# clipper.net
KiCad netlist of a schematic drawn in EAGLE
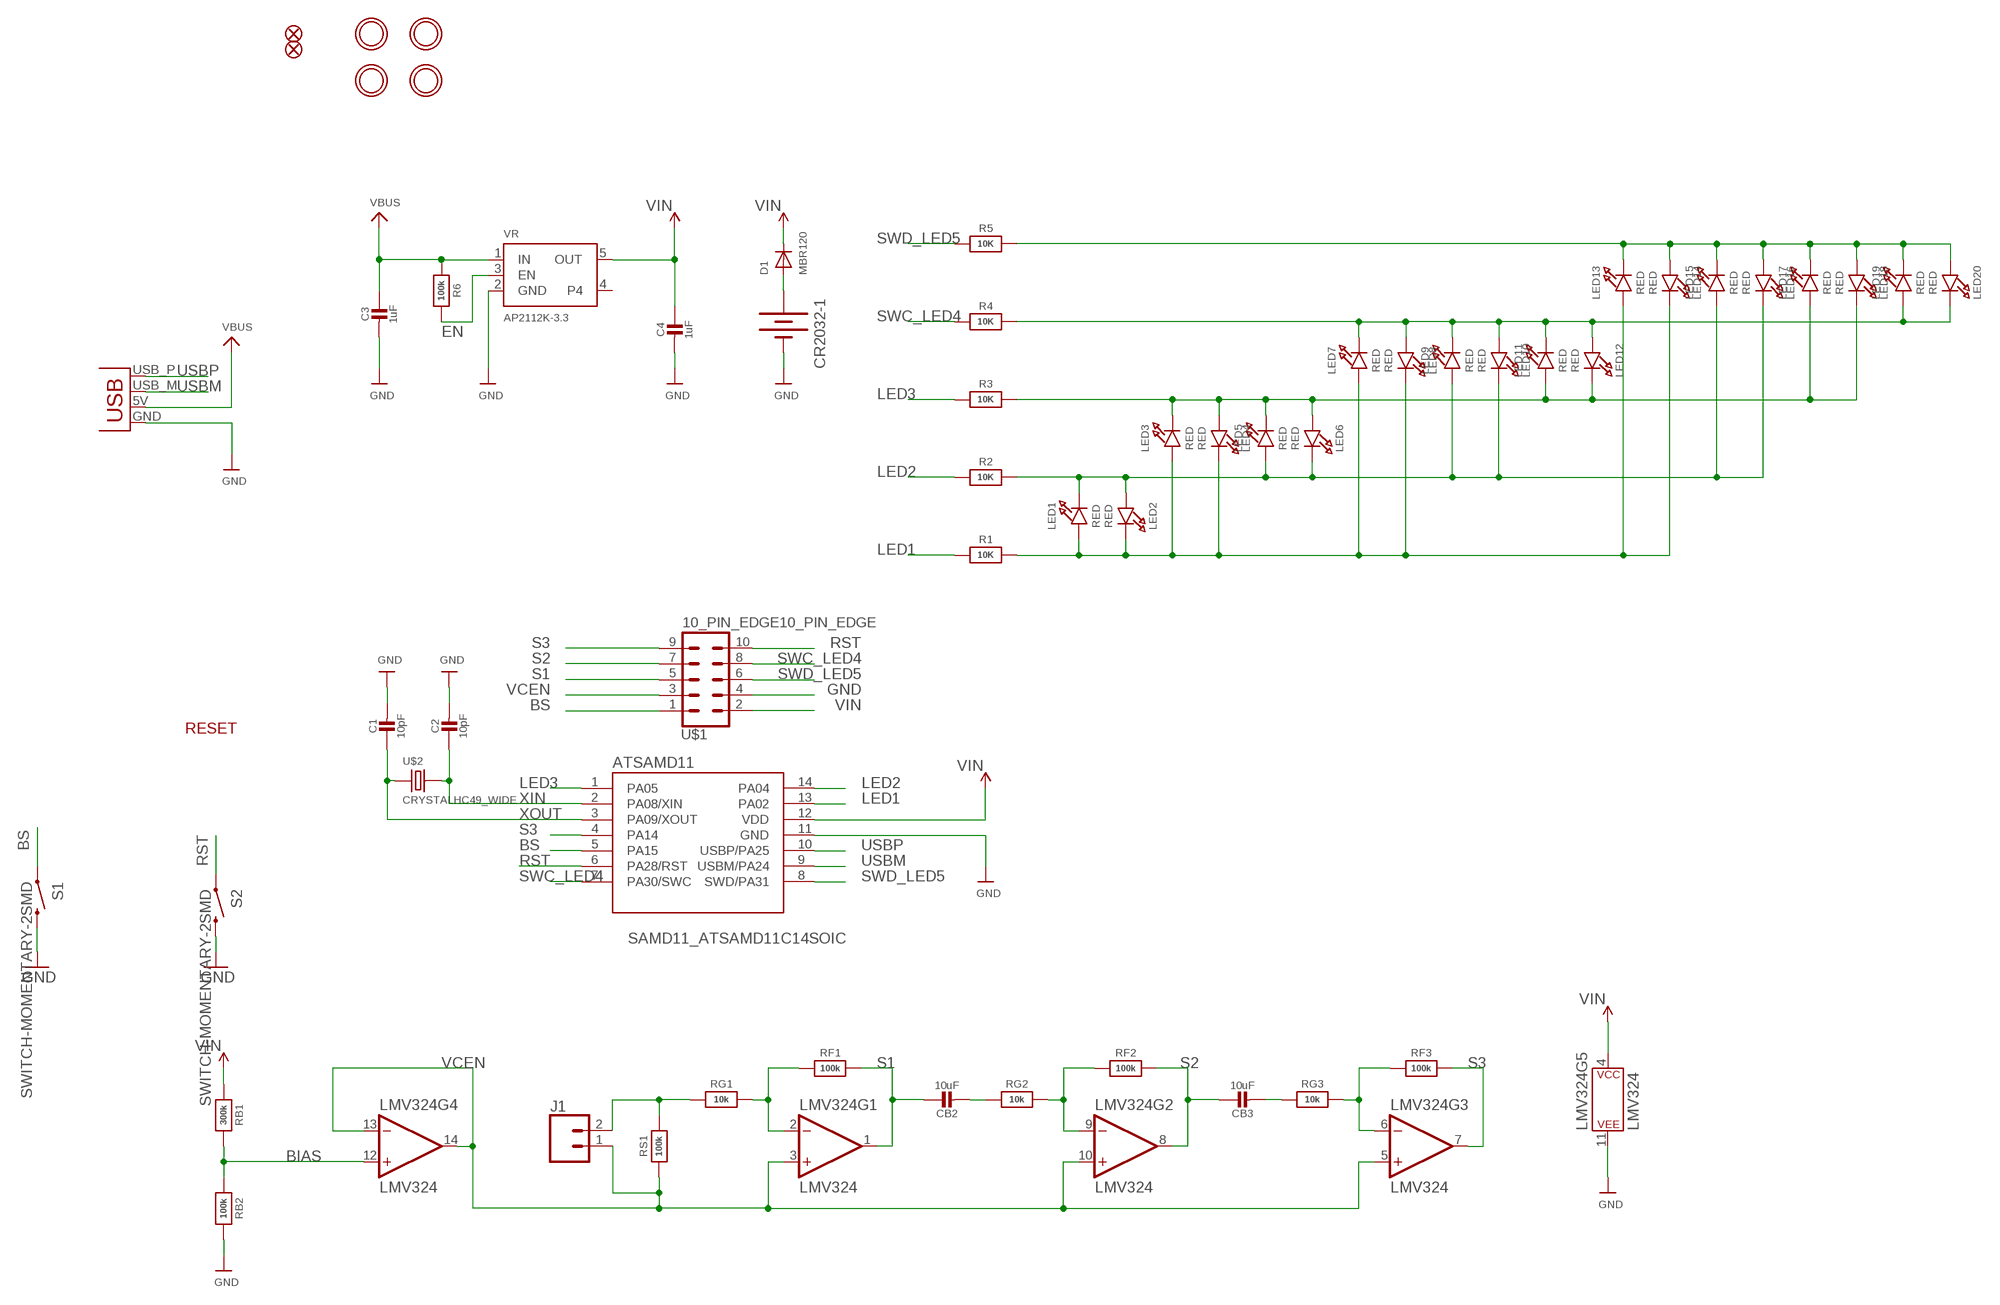
[diagram p0: schematic, sheet 1]

(export (version "E")
  (design (tool "Eeschema 10.0.6"))
  (components
    (comp (ref "ATSAMD11")
      (value "SAMD11_ATSAMD11C14SOIC")
      (footprint "eagle-import:RRACE001_SO14")
      (libsource (lib "eagle-import") (part "SAMD11_ATSAMD11C14SOIC"))
    )
    (comp (ref "C1")
      (value "10pF")
      (footprint "eagle-import:0603-NO")
      (libsource (lib "eagle-import") (part "CAP_CERAMIC0603_NO"))
    )
    (comp (ref "C2")
      (value "10pF")
      (footprint "eagle-import:0603-NO")
      (libsource (lib "eagle-import") (part "CAP_CERAMIC0603_NO"))
    )
    (comp (ref "C3")
      (value "1uF")
      (footprint "eagle-import:0603-NO")
      (libsource (lib "eagle-import") (part "CAP_CERAMIC0603_NO"))
    )
    (comp (ref "C4")
      (value "1uF")
      (footprint "eagle-import:0603-NO")
      (libsource (lib "eagle-import") (part "CAP_CERAMIC0603_NO"))
    )
    (comp (ref "CB2")
      (value "10uF")
      (footprint "eagle-import:0603-NO")
      (libsource (lib "eagle-import") (part "CAP_CERAMIC0603_NO"))
    )
    (comp (ref "CB3")
      (value "10uF")
      (footprint "eagle-import:0603-NO")
      (libsource (lib "eagle-import") (part "CAP_CERAMIC0603_NO"))
    )
    (comp (ref "CR2032-1")
      (value "BATTERY_20MM_PTH")
      (footprint "eagle-import:BATTCOM_20MM_PTH")
      (libsource (lib "eagle-import") (part "BATTERY_20MM_PTH"))
    )
    (comp (ref "D1")
      (value "MBR120")
      (footprint "eagle-import:SOD-123FL")
      (libsource (lib "eagle-import") (part "DIODE_SOD-123FL"))
    )
    (comp (ref "J1")
      (value "CONN_02")
      (footprint "eagle-import:1X02")
      (libsource (lib "eagle-import") (part "CONN_02"))
    )
    (comp (ref "LED1")
      (value "RED")
      (footprint "eagle-import:CHIPLED_0603_NOOUTLINE")
      (libsource (lib "eagle-import") (part "LED0603_NOOUTLINE"))
    )
    (comp (ref "LED2")
      (value "RED")
      (footprint "eagle-import:CHIPLED_0603_NOOUTLINE")
      (libsource (lib "eagle-import") (part "LED0603_NOOUTLINE"))
    )
    (comp (ref "LED3")
      (value "RED")
      (footprint "eagle-import:CHIPLED_0603_NOOUTLINE")
      (libsource (lib "eagle-import") (part "LED0603_NOOUTLINE"))
    )
    (comp (ref "LED4")
      (value "RED")
      (footprint "eagle-import:CHIPLED_0603_NOOUTLINE")
      (libsource (lib "eagle-import") (part "LED0603_NOOUTLINE"))
    )
    (comp (ref "LED5")
      (value "RED")
      (footprint "eagle-import:CHIPLED_0603_NOOUTLINE")
      (libsource (lib "eagle-import") (part "LED0603_NOOUTLINE"))
    )
    (comp (ref "LED6")
      (value "RED")
      (footprint "eagle-import:CHIPLED_0603_NOOUTLINE")
      (libsource (lib "eagle-import") (part "LED0603_NOOUTLINE"))
    )
    (comp (ref "LED7")
      (value "RED")
      (footprint "eagle-import:CHIPLED_0603_NOOUTLINE")
      (libsource (lib "eagle-import") (part "LED0603_NOOUTLINE"))
    )
    (comp (ref "LED8")
      (value "RED")
      (footprint "eagle-import:CHIPLED_0603_NOOUTLINE")
      (libsource (lib "eagle-import") (part "LED0603_NOOUTLINE"))
    )
    (comp (ref "LED9")
      (value "RED")
      (footprint "eagle-import:CHIPLED_0603_NOOUTLINE")
      (libsource (lib "eagle-import") (part "LED0603_NOOUTLINE"))
    )
    (comp (ref "LED10")
      (value "RED")
      (footprint "eagle-import:CHIPLED_0603_NOOUTLINE")
      (libsource (lib "eagle-import") (part "LED0603_NOOUTLINE"))
    )
    (comp (ref "LED11")
      (value "RED")
      (footprint "eagle-import:CHIPLED_0603_NOOUTLINE")
      (libsource (lib "eagle-import") (part "LED0603_NOOUTLINE"))
    )
    (comp (ref "LED12")
      (value "RED")
      (footprint "eagle-import:CHIPLED_0603_NOOUTLINE")
      (libsource (lib "eagle-import") (part "LED0603_NOOUTLINE"))
    )
    (comp (ref "LED13")
      (value "RED")
      (footprint "eagle-import:CHIPLED_0603_NOOUTLINE")
      (libsource (lib "eagle-import") (part "LED0603_NOOUTLINE"))
    )
    (comp (ref "LED14")
      (value "RED")
      (footprint "eagle-import:CHIPLED_0603_NOOUTLINE")
      (libsource (lib "eagle-import") (part "LED0603_NOOUTLINE"))
    )
    (comp (ref "LED15")
      (value "RED")
      (footprint "eagle-import:CHIPLED_0603_NOOUTLINE")
      (libsource (lib "eagle-import") (part "LED0603_NOOUTLINE"))
    )
    (comp (ref "LED16")
      (value "RED")
      (footprint "eagle-import:CHIPLED_0603_NOOUTLINE")
      (libsource (lib "eagle-import") (part "LED0603_NOOUTLINE"))
    )
    (comp (ref "LED17")
      (value "RED")
      (footprint "eagle-import:CHIPLED_0603_NOOUTLINE")
      (libsource (lib "eagle-import") (part "LED0603_NOOUTLINE"))
    )
    (comp (ref "LED18")
      (value "RED")
      (footprint "eagle-import:CHIPLED_0603_NOOUTLINE")
      (libsource (lib "eagle-import") (part "LED0603_NOOUTLINE"))
    )
    (comp (ref "LED19")
      (value "RED")
      (footprint "eagle-import:CHIPLED_0603_NOOUTLINE")
      (libsource (lib "eagle-import") (part "LED0603_NOOUTLINE"))
    )
    (comp (ref "LED20")
      (value "RED")
      (footprint "eagle-import:CHIPLED_0603_NOOUTLINE")
      (libsource (lib "eagle-import") (part "LED0603_NOOUTLINE"))
    )
    (comp (ref "LMV324")
      (value "LMV324")
      (footprint "eagle-import:SO14")
      (libsource (lib "eagle-import") (part "LMV324SO14"))
    )
    (comp (ref "MH1")
      (value "MOUNTINGHOLE2.5")
      (footprint "eagle-import:MOUNTINGHOLE_2.5_PLATED")
      (libsource (lib "eagle-import") (part "MOUNTINGHOLE2.5"))
    )
    (comp (ref "MH2")
      (value "MOUNTINGHOLE2.5")
      (footprint "eagle-import:MOUNTINGHOLE_2.5_PLATED")
      (libsource (lib "eagle-import") (part "MOUNTINGHOLE2.5"))
    )
    (comp (ref "MH3")
      (value "MOUNTINGHOLE2.5")
      (footprint "eagle-import:MOUNTINGHOLE_2.5_PLATED")
      (libsource (lib "eagle-import") (part "MOUNTINGHOLE2.5"))
    )
    (comp (ref "MH4")
      (value "MOUNTINGHOLE2.5")
      (footprint "eagle-import:MOUNTINGHOLE_2.5_PLATED")
      (libsource (lib "eagle-import") (part "MOUNTINGHOLE2.5"))
    )
    (comp (ref "R1")
      (value "10K")
      (footprint "eagle-import:0603-NO")
      (libsource (lib "eagle-import") (part "RESISTOR_0603_NOOUT"))
    )
    (comp (ref "R2")
      (value "10K")
      (footprint "eagle-import:0603-NO")
      (libsource (lib "eagle-import") (part "RESISTOR_0603_NOOUT"))
    )
    (comp (ref "R3")
      (value "10K")
      (footprint "eagle-import:0603-NO")
      (libsource (lib "eagle-import") (part "RESISTOR_0603_NOOUT"))
    )
    (comp (ref "R4")
      (value "10K")
      (footprint "eagle-import:0603-NO")
      (libsource (lib "eagle-import") (part "RESISTOR_0603_NOOUT"))
    )
    (comp (ref "R5")
      (value "10K")
      (footprint "eagle-import:0603-NO")
      (libsource (lib "eagle-import") (part "RESISTOR_0603_NOOUT"))
    )
    (comp (ref "R6")
      (value "100k")
      (footprint "eagle-import:0603-NO")
      (libsource (lib "eagle-import") (part "RESISTOR_0603_NOOUT"))
    )
    (comp (ref "RB1")
      (value "300k")
      (footprint "eagle-import:0603-NO")
      (libsource (lib "eagle-import") (part "RESISTOR_0603_NOOUT"))
    )
    (comp (ref "RB2")
      (value "100k")
      (footprint "eagle-import:0603-NO")
      (libsource (lib "eagle-import") (part "RESISTOR_0603_NOOUT"))
    )
    (comp (ref "RF1")
      (value "100k")
      (footprint "eagle-import:0603-NO")
      (libsource (lib "eagle-import") (part "RESISTOR_0603_NOOUT"))
    )
    (comp (ref "RF2")
      (value "100k")
      (footprint "eagle-import:0603-NO")
      (libsource (lib "eagle-import") (part "RESISTOR_0603_NOOUT"))
    )
    (comp (ref "RF3")
      (value "100k")
      (footprint "eagle-import:0603-NO")
      (libsource (lib "eagle-import") (part "RESISTOR_0603_NOOUT"))
    )
    (comp (ref "RG1")
      (value "10k")
      (footprint "eagle-import:0603-NO")
      (libsource (lib "eagle-import") (part "RESISTOR_0603_NOOUT"))
    )
    (comp (ref "RG2")
      (value "10k")
      (footprint "eagle-import:0603-NO")
      (libsource (lib "eagle-import") (part "RESISTOR_0603_NOOUT"))
    )
    (comp (ref "RG3")
      (value "10k")
      (footprint "eagle-import:0603-NO")
      (libsource (lib "eagle-import") (part "RESISTOR_0603_NOOUT"))
    )
    (comp (ref "RS1")
      (value "100k")
      (footprint "eagle-import:0603-NO")
      (libsource (lib "eagle-import") (part "RESISTOR_0603_NOOUT"))
    )
    (comp (ref "S1")
      (value "SWITCH-MOMENTARY-2SMD")
      (footprint "eagle-import:TACTILE-SWITCH-SMD")
      (libsource (lib "eagle-import") (part "SWITCH-MOMENTARY-2SMD"))
    )
    (comp (ref "S2")
      (value "SWITCH-MOMENTARY-2SMD")
      (footprint "eagle-import:TACTILE-SWITCH-SMD")
      (libsource (lib "eagle-import") (part "SWITCH-MOMENTARY-2SMD"))
    )
    (comp (ref "U$1")
      (value "10_PIN_EDGE10_PIN_EDGE")
      (footprint "eagle-import:10_PIN_EDGE")
      (libsource (lib "eagle-import") (part "10_PIN_EDGE10_PIN_EDGE"))
    )
    (comp (ref "U$2")
      (value "CRYSTALHC49_WIDE")
      (footprint "eagle-import:HC49U_ALL")
      (libsource (lib "eagle-import") (part "CRYSTALHC49_WIDE"))
    )
    (comp (ref "U$34")
      (value "FIDUCIAL_1MM")
      (footprint "eagle-import:FIDUCIAL_1MM")
      (libsource (lib "eagle-import") (part "FIDUCIAL_1MM"))
    )
    (comp (ref "U$35")
      (value "FIDUCIAL_1MM")
      (footprint "eagle-import:FIDUCIAL_1MM")
      (libsource (lib "eagle-import") (part "FIDUCIAL_1MM"))
    )
    (comp (ref "VR")
      (value "AP2112K-3.3")
      (footprint "eagle-import:SOT23-5")
      (libsource (lib "eagle-import") (part "VREG_SOT23-5"))
    )
    (comp (ref "X4")
      (value "USBPCB")
      (footprint "eagle-import:USB-A-PCB")
      (libsource (lib "eagle-import") (part "USBPCB"))
    )
  )
  (nets
    (net (code "1") (name "/BIAS") (class "Default")
      (node (ref "LMV324") (pin "12") (pinfunction "+IN_12") (pintype "input"))
      (node (ref "RB1") (pin "2") (pinfunction "2_2") (pintype "passive"))
      (node (ref "RB2") (pin "1") (pinfunction "1_1") (pintype "passive"))
    )
    (net (code "2") (name "/BS") (class "Default")
      (node (ref "ATSAMD11") (pin "5") (pinfunction "PA15_5") (pintype "bidirectional"))
      (node (ref "S1") (pin "1") (pinfunction "1_1") (pintype "passive"))
      (node (ref "U$1") (pin "1") (pinfunction "1_1") (pintype "passive"))
    )
    (net (code "3") (name "/EN") (class "Default")
      (node (ref "R6") (pin "2") (pinfunction "2_2") (pintype "passive"))
      (node (ref "VR") (pin "3") (pinfunction "EN_3") (pintype "input"))
    )
    (net (code "4") (name "/LED1") (class "Default")
      (node (ref "ATSAMD11") (pin "13") (pinfunction "PA02_13") (pintype "bidirectional"))
      (node (ref "R1") (pin "1") (pinfunction "1_1") (pintype "passive"))
    )
    (net (code "5") (name "/LED2") (class "Default")
      (node (ref "ATSAMD11") (pin "14") (pinfunction "PA04_14") (pintype "bidirectional"))
      (node (ref "R2") (pin "1") (pinfunction "1_1") (pintype "passive"))
    )
    (net (code "6") (name "/LED3") (class "Default")
      (node (ref "ATSAMD11") (pin "1") (pinfunction "PA05_1") (pintype "bidirectional"))
      (node (ref "R3") (pin "1") (pinfunction "1_1") (pintype "passive"))
    )
    (net (code "7") (name "/RST") (class "Default")
      (node (ref "ATSAMD11") (pin "6") (pinfunction "PA28/RST_6") (pintype "bidirectional"))
      (node (ref "S2") (pin "1") (pinfunction "1_1") (pintype "passive"))
      (node (ref "U$1") (pin "10") (pinfunction "10_10") (pintype "passive"))
    )
    (net (code "8") (name "/S1") (class "Default")
      (node (ref "CB2") (pin "1") (pinfunction "1_1") (pintype "passive"))
      (node (ref "LMV324") (pin "1") (pinfunction "OUT_1") (pintype "output"))
      (node (ref "RF1") (pin "2") (pinfunction "2_2") (pintype "passive"))
      (node (ref "U$1") (pin "5") (pinfunction "5_5") (pintype "passive"))
    )
    (net (code "9") (name "/S2") (class "Default")
      (node (ref "CB3") (pin "1") (pinfunction "1_1") (pintype "passive"))
      (node (ref "LMV324") (pin "8") (pinfunction "OUT_8") (pintype "output"))
      (node (ref "RF2") (pin "2") (pinfunction "2_2") (pintype "passive"))
      (node (ref "U$1") (pin "7") (pinfunction "7_7") (pintype "passive"))
    )
    (net (code "10") (name "/S3") (class "Default")
      (node (ref "ATSAMD11") (pin "4") (pinfunction "PA14_4") (pintype "bidirectional"))
      (node (ref "LMV324") (pin "7") (pinfunction "OUT_7") (pintype "output"))
      (node (ref "RF3") (pin "2") (pinfunction "2_2") (pintype "passive"))
      (node (ref "U$1") (pin "9") (pinfunction "9_9") (pintype "passive"))
    )
    (net (code "11") (name "/SWC_LED4") (class "Default")
      (node (ref "ATSAMD11") (pin "7") (pinfunction "PA30/SWC_7") (pintype "bidirectional"))
      (node (ref "R4") (pin "1") (pinfunction "1_1") (pintype "passive"))
      (node (ref "U$1") (pin "8") (pinfunction "8_8") (pintype "passive"))
    )
    (net (code "12") (name "/SWD_LED5") (class "Default")
      (node (ref "ATSAMD11") (pin "8") (pinfunction "SWD/PA31_8") (pintype "bidirectional"))
      (node (ref "R5") (pin "1") (pinfunction "1_1") (pintype "passive"))
      (node (ref "U$1") (pin "6") (pinfunction "6_6") (pintype "passive"))
    )
    (net (code "13") (name "/USBM") (class "Default")
      (node (ref "ATSAMD11") (pin "9") (pinfunction "USBM/PA24_9") (pintype "bidirectional"))
      (node (ref "X4") (pin "USB_M") (pinfunction "D-_USB_M") (pintype "bidirectional"))
    )
    (net (code "14") (name "/USBP") (class "Default")
      (node (ref "ATSAMD11") (pin "10") (pinfunction "USBP/PA25_10") (pintype "bidirectional"))
      (node (ref "X4") (pin "USB_P") (pinfunction "D+_USB_P") (pintype "bidirectional"))
    )
    (net (code "15") (name "/VCEN") (class "Default")
      (node (ref "J1") (pin "1") (pinfunction "1_1") (pintype "passive"))
      (node (ref "LMV324") (pin "10") (pinfunction "+IN_10") (pintype "input"))
      (node (ref "LMV324") (pin "13") (pinfunction "-IN_13") (pintype "input"))
      (node (ref "LMV324") (pin "14") (pinfunction "OUT_14") (pintype "output"))
      (node (ref "LMV324") (pin "3") (pinfunction "+IN_3") (pintype "input"))
      (node (ref "LMV324") (pin "5") (pinfunction "+IN_5") (pintype "input"))
      (node (ref "RS1") (pin "1") (pinfunction "1_1") (pintype "passive"))
      (node (ref "U$1") (pin "3") (pinfunction "3_3") (pintype "passive"))
    )
    (net (code "16") (name "/XIN") (class "Default")
      (node (ref "ATSAMD11") (pin "2") (pinfunction "PA08/XIN_2") (pintype "bidirectional"))
      (node (ref "C2") (pin "1") (pinfunction "1_1") (pintype "passive"))
      (node (ref "U$2") (pin "2") (pinfunction "2_2") (pintype "passive"))
    )
    (net (code "17") (name "/XOUT") (class "Default")
      (node (ref "ATSAMD11") (pin "3") (pinfunction "PA09/XOUT_3") (pintype "bidirectional"))
      (node (ref "C1") (pin "1") (pinfunction "1_1") (pintype "passive"))
      (node (ref "U$2") (pin "1") (pinfunction "1_1") (pintype "passive"))
    )
    (net (code "18") (name "GND") (class "Default")
      (node (ref "ATSAMD11") (pin "11") (pinfunction "GND_11") (pintype "bidirectional"))
      (node (ref "C1") (pin "2") (pinfunction "2_2") (pintype "passive"))
      (node (ref "C2") (pin "2") (pinfunction "2_2") (pintype "passive"))
      (node (ref "C3") (pin "2") (pinfunction "2_2") (pintype "passive"))
      (node (ref "C4") (pin "2") (pinfunction "2_2") (pintype "passive"))
      (node (ref "CR2032-1") (pin "NEG") (pinfunction "-_NEG") (pintype "power_in"))
      (node (ref "LMV324") (pin "11") (pinfunction "P$V-_11") (pintype "bidirectional"))
      (node (ref "RB2") (pin "2") (pinfunction "2_2") (pintype "passive"))
      (node (ref "S1") (pin "3") (pinfunction "2_3") (pintype "passive"))
      (node (ref "S2") (pin "3") (pinfunction "2_3") (pintype "passive"))
      (node (ref "U$1") (pin "4") (pinfunction "4_4") (pintype "passive"))
      (node (ref "VR") (pin "2") (pinfunction "GND_2") (pintype "power_in"))
      (node (ref "X4") (pin "GND") (pinfunction "GND_GND") (pintype "bidirectional"))
    )
    (net (code "19") (name "Net-(CB2-Pad2)") (class "Default")
      (node (ref "CB2") (pin "2") (pinfunction "2_2") (pintype "passive"))
      (node (ref "RG2") (pin "1") (pinfunction "1_1") (pintype "passive"))
    )
    (net (code "20") (name "Net-(CB3-Pad2)") (class "Default")
      (node (ref "CB3") (pin "2") (pinfunction "2_2") (pintype "passive"))
      (node (ref "RG3") (pin "1") (pinfunction "1_1") (pintype "passive"))
    )
    (net (code "21") (name "Net-(CR2032-1-+)") (class "Default")
      (node (ref "CR2032-1") (pin "POS") (pinfunction "+_POS") (pintype "power_in"))
      (node (ref "D1") (pin "A") (pinfunction "A_A") (pintype "passive"))
    )
    (net (code "22") (name "Net-(J1-Pad2)") (class "Default")
      (node (ref "J1") (pin "2") (pinfunction "2_2") (pintype "passive"))
      (node (ref "RG1") (pin "1") (pinfunction "1_1") (pintype "passive"))
      (node (ref "RS1") (pin "2") (pinfunction "2_2") (pintype "passive"))
    )
    (net (code "23") (name "Net-(LED1-PadA)") (class "Default")
      (node (ref "LED1") (pin "A") (pinfunction "A_A") (pintype "passive"))
      (node (ref "LED13") (pin "A") (pinfunction "A_A") (pintype "passive"))
      (node (ref "LED14") (pin "C") (pinfunction "C_C") (pintype "passive"))
      (node (ref "LED2") (pin "C") (pinfunction "C_C") (pintype "passive"))
      (node (ref "LED3") (pin "A") (pinfunction "A_A") (pintype "passive"))
      (node (ref "LED4") (pin "C") (pinfunction "C_C") (pintype "passive"))
      (node (ref "LED7") (pin "A") (pinfunction "A_A") (pintype "passive"))
      (node (ref "LED8") (pin "C") (pinfunction "C_C") (pintype "passive"))
      (node (ref "R1") (pin "2") (pinfunction "2_2") (pintype "passive"))
    )
    (net (code "24") (name "Net-(LED1-PadC)") (class "Default")
      (node (ref "LED1") (pin "C") (pinfunction "C_C") (pintype "passive"))
      (node (ref "LED10") (pin "C") (pinfunction "C_C") (pintype "passive"))
      (node (ref "LED15") (pin "A") (pinfunction "A_A") (pintype "passive"))
      (node (ref "LED16") (pin "C") (pinfunction "C_C") (pintype "passive"))
      (node (ref "LED2") (pin "A") (pinfunction "A_A") (pintype "passive"))
      (node (ref "LED5") (pin "A") (pinfunction "A_A") (pintype "passive"))
      (node (ref "LED6") (pin "C") (pinfunction "C_C") (pintype "passive"))
      (node (ref "LED9") (pin "A") (pinfunction "A_A") (pintype "passive"))
      (node (ref "R2") (pin "2") (pinfunction "2_2") (pintype "passive"))
    )
    (net (code "25") (name "Net-(LED10-PadA)") (class "Default")
      (node (ref "LED10") (pin "A") (pinfunction "A_A") (pintype "passive"))
      (node (ref "LED11") (pin "C") (pinfunction "C_C") (pintype "passive"))
      (node (ref "LED12") (pin "A") (pinfunction "A_A") (pintype "passive"))
      (node (ref "LED19") (pin "A") (pinfunction "A_A") (pintype "passive"))
      (node (ref "LED20") (pin "C") (pinfunction "C_C") (pintype "passive"))
      (node (ref "LED7") (pin "C") (pinfunction "C_C") (pintype "passive"))
      (node (ref "LED8") (pin "A") (pinfunction "A_A") (pintype "passive"))
      (node (ref "LED9") (pin "C") (pinfunction "C_C") (pintype "passive"))
      (node (ref "R4") (pin "2") (pinfunction "2_2") (pintype "passive"))
    )
    (net (code "26") (name "Net-(LED11-PadA)") (class "Default")
      (node (ref "LED11") (pin "A") (pinfunction "A_A") (pintype "passive"))
      (node (ref "LED12") (pin "C") (pinfunction "C_C") (pintype "passive"))
      (node (ref "LED17") (pin "A") (pinfunction "A_A") (pintype "passive"))
      (node (ref "LED18") (pin "C") (pinfunction "C_C") (pintype "passive"))
      (node (ref "LED3") (pin "C") (pinfunction "C_C") (pintype "passive"))
      (node (ref "LED4") (pin "A") (pinfunction "A_A") (pintype "passive"))
      (node (ref "LED5") (pin "C") (pinfunction "C_C") (pintype "passive"))
      (node (ref "LED6") (pin "A") (pinfunction "A_A") (pintype "passive"))
      (node (ref "R3") (pin "2") (pinfunction "2_2") (pintype "passive"))
    )
    (net (code "27") (name "Net-(LED13-PadC)") (class "Default")
      (node (ref "LED13") (pin "C") (pinfunction "C_C") (pintype "passive"))
      (node (ref "LED14") (pin "A") (pinfunction "A_A") (pintype "passive"))
      (node (ref "LED15") (pin "C") (pinfunction "C_C") (pintype "passive"))
      (node (ref "LED16") (pin "A") (pinfunction "A_A") (pintype "passive"))
      (node (ref "LED17") (pin "C") (pinfunction "C_C") (pintype "passive"))
      (node (ref "LED18") (pin "A") (pinfunction "A_A") (pintype "passive"))
      (node (ref "LED19") (pin "C") (pinfunction "C_C") (pintype "passive"))
      (node (ref "LED20") (pin "A") (pinfunction "A_A") (pintype "passive"))
      (node (ref "R5") (pin "2") (pinfunction "2_2") (pintype "passive"))
    )
    (net (code "28") (name "Net-(LMV324A--IN)") (class "Default")
      (node (ref "LMV324") (pin "2") (pinfunction "-IN_2") (pintype "input"))
      (node (ref "RF1") (pin "1") (pinfunction "1_1") (pintype "passive"))
      (node (ref "RG1") (pin "2") (pinfunction "2_2") (pintype "passive"))
    )
    (net (code "29") (name "Net-(LMV324B--IN)") (class "Default")
      (node (ref "LMV324") (pin "9") (pinfunction "-IN_9") (pintype "input"))
      (node (ref "RF2") (pin "1") (pinfunction "1_1") (pintype "passive"))
      (node (ref "RG2") (pin "2") (pinfunction "2_2") (pintype "passive"))
    )
    (net (code "30") (name "Net-(LMV324C--IN)") (class "Default")
      (node (ref "LMV324") (pin "6") (pinfunction "-IN_6") (pintype "input"))
      (node (ref "RF3") (pin "1") (pinfunction "1_1") (pintype "passive"))
      (node (ref "RG3") (pin "2") (pinfunction "2_2") (pintype "passive"))
    )
    (net (code "31") (name "VBUS") (class "Default")
      (node (ref "C3") (pin "1") (pinfunction "1_1") (pintype "passive"))
      (node (ref "R6") (pin "1") (pinfunction "1_1") (pintype "passive"))
      (node (ref "VR") (pin "1") (pinfunction "IN_1") (pintype "power_in"))
      (node (ref "X4") (pin "5V") (pinfunction "VBUS_5V") (pintype "bidirectional"))
    )
    (net (code "32") (name "VIN") (class "Default")
      (node (ref "ATSAMD11") (pin "12") (pinfunction "VDD_12") (pintype "bidirectional"))
      (node (ref "C4") (pin "1") (pinfunction "1_1") (pintype "passive"))
      (node (ref "D1") (pin "C") (pinfunction "C_C") (pintype "passive"))
      (node (ref "LMV324") (pin "4") (pinfunction "P$V+_4") (pintype "bidirectional"))
      (node (ref "RB1") (pin "1") (pinfunction "1_1") (pintype "passive"))
      (node (ref "U$1") (pin "2") (pinfunction "2_2") (pintype "passive"))
      (node (ref "VR") (pin "5") (pinfunction "OUT_5") (pintype "power_in"))
    )
    (net (code "33") (name "unconnected-(VR-P4-Pad4)") (class "Default")
      (node (ref "VR") (pin "4") (pinfunction "P4_4") (pintype "bidirectional"))
    )
  )
)
